# Enable.net
KiCad netlist of a schematic drawn in Altium Designer
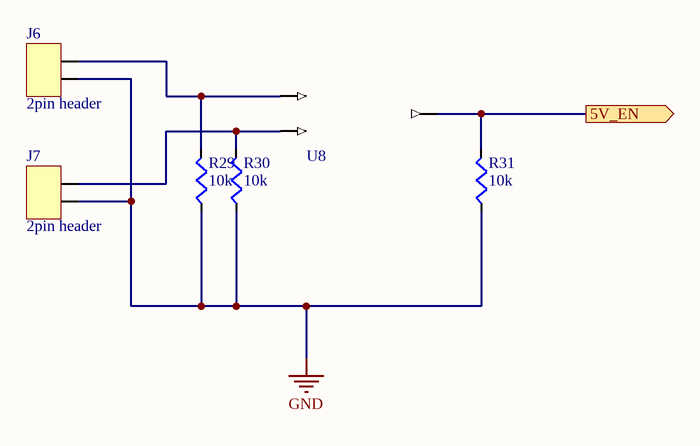
[diagram p0: Enable.SchDoc]

(export (version "E")
  (design (tool "Eeschema 10.0.6"))
  (components
    (comp (ref "J6") (value "2pin header") (footprint "HEADERPINS_2x1") (libsource (lib "DAQ") (part "J2")))
    (comp (ref "J7") (value "2pin header") (footprint "HEADERPINS_2x1") (libsource (lib "DAQ") (part "J2")))
    (comp (ref "R29")
      (value "10k")
      (footprint "R0603")
      (description "RES SMD 10K OHM 5% 1/10W 0603")
      (libsource (lib "DAQ") (part "RC0603JR-0710KL"))
    )
    (comp (ref "R30")
      (value "10k")
      (footprint "R0603")
      (description "RES SMD 10K OHM 5% 1/10W 0603")
      (libsource (lib "DAQ") (part "RC0603JR-0710KL"))
    )
    (comp (ref "R31")
      (value "10k")
      (footprint "R0603")
      (description "RES SMD 10K OHM 5% 1/10W 0603")
      (libsource (lib "DAQ") (part "RC0603JR-0710KL"))
    )
    (comp (ref "U8")
      (value "AND")
      (description "AND Gate 1-Element 2-IN CMOS Automotive 5-Pin SC-88A T/R")
      (libsource (lib "DAQ") (part "MC74VHC1G08DFT2G"))
    )
  )
  (nets
    (net (code "1") (name "/5V_EN") (class "Default")
      (node (ref "R31") (pin "2") (pinfunction "2_2") (pintype "passive"))
      (node (ref "U8") (pin "19") (pintype "output"))
    )
    (net (code "2") (name "GND") (class "Default")
      (node (ref "J6") (pin "2") (pinfunction "2_2") (pintype "passive"))
      (node (ref "J7") (pin "2") (pinfunction "2_2") (pintype "passive"))
      (node (ref "R29") (pin "1") (pinfunction "1_1") (pintype "passive"))
      (node (ref "R30") (pin "1") (pinfunction "1_1") (pintype "passive"))
      (node (ref "R31") (pin "1") (pinfunction "1_1") (pintype "passive"))
    )
    (net (code "3") (name "Net-(J6-Pad1)") (class "Default")
      (node (ref "J6") (pin "1") (pinfunction "1_1") (pintype "passive"))
      (node (ref "R29") (pin "2") (pinfunction "2_2") (pintype "passive"))
      (node (ref "U8") (pin "17") (pintype "input"))
    )
    (net (code "4") (name "Net-(J7-Pad1)") (class "Default")
      (node (ref "J7") (pin "1") (pinfunction "1_1") (pintype "passive"))
      (node (ref "R30") (pin "2") (pinfunction "2_2") (pintype "passive"))
      (node (ref "U8") (pin "18") (pintype "input"))
    )
  )
)
